# WeMosMid400Sensor.net
KiCad netlist of a schematic drawn in EAGLE
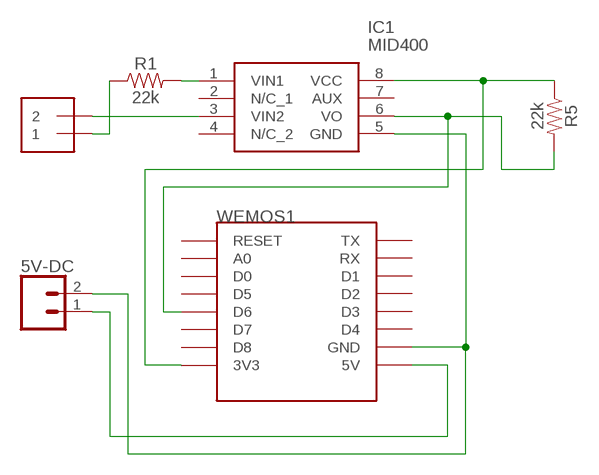
[diagram p0: schematic, sheet 1]

(export (version "E")
  (design (tool "Eeschema 10.0.6"))
  (components
    (comp (ref "5V-DC")
      (value "CONN_02")
      (footprint "eagle-import:1X02")
      (libsource (lib "eagle-import") (part "CONN_02"))
    )
    (comp (ref "A/C")
      (value "1X2-3.5MM")
      (footprint "eagle-import:1X2-3.5MM")
      (libsource (lib "eagle-import") (part "1X2-3.5MM"))
    )
    (comp (ref "IC1")
      (value "MID400")
      (footprint "eagle-import:DIP762W56P254L966H508Q8N")
      (fields (field (name "RS_PART_NUMBER") "7613962P"))
      (libsource (lib "eagle-import") (part "MID400"))
    )
    (comp (ref "R1")
      (value "22k")
      (footprint "eagle-import:AXIAL-0.3")
      (libsource (lib "eagle-import") (part "15KOHM-HORIZ-1/4W-5%"))
    )
    (comp (ref "R5")
      (value "22k")
      (footprint "eagle-import:AXIAL-0.3")
      (libsource (lib "eagle-import") (part "15KOHM-HORIZ-1/4W-5%"))
    )
    (comp (ref "WEMOS1")
      (value "WEMOS-D1-MINI")
      (footprint "eagle-import:WEMOS-D1-MINI")
      (libsource (lib "eagle-import") (part "WEMOS-D1-MINI"))
    )
  )
  (nets
    (net (code "1") (name "Net-(5V-DC-Pad1)") (class "Default")
      (node (ref "5V-DC") (pin "1") (pinfunction "1_1") (pintype "passive"))
      (node (ref "WEMOS1") (pin "5V") (pinfunction "5V_5V") (pintype "bidirectional"))
    )
    (net (code "2") (name "Net-(IC1-GND)") (class "Default")
      (node (ref "5V-DC") (pin "2") (pinfunction "2_2") (pintype "passive"))
      (node (ref "IC1") (pin "5") (pinfunction "GND_5") (pintype "bidirectional"))
      (node (ref "WEMOS1") (pin "GND") (pinfunction "GND_GND") (pintype "bidirectional"))
    )
    (net (code "3") (name "Net-(IC1-VCC)") (class "Default")
      (node (ref "IC1") (pin "8") (pinfunction "VCC_8") (pintype "bidirectional"))
      (node (ref "R5") (pin "P$1") (pinfunction "1_P$1") (pintype "passive"))
      (node (ref "WEMOS1") (pin "3V3") (pinfunction "3V3_3V3") (pintype "bidirectional"))
    )
    (net (code "4") (name "Net-(IC1-VIN1)") (class "Default")
      (node (ref "IC1") (pin "1") (pinfunction "VIN1_1") (pintype "bidirectional"))
      (node (ref "R1") (pin "P$2") (pinfunction "2_P$2") (pintype "passive"))
    )
    (net (code "5") (name "Net-(IC1-VIN2)") (class "Default")
      (node (ref "A/C") (pin "2") (pinfunction "2_2") (pintype "passive"))
      (node (ref "IC1") (pin "3") (pinfunction "VIN2_3") (pintype "bidirectional"))
    )
    (net (code "6") (name "Net-(IC1-VO)") (class "Default")
      (node (ref "IC1") (pin "6") (pinfunction "VO_6") (pintype "bidirectional"))
      (node (ref "R5") (pin "P$2") (pinfunction "2_P$2") (pintype "passive"))
      (node (ref "WEMOS1") (pin "D6") (pinfunction "D6_D6") (pintype "bidirectional"))
    )
    (net (code "7") (name "Net-(R1-1)") (class "Default")
      (node (ref "A/C") (pin "1") (pinfunction "1_1") (pintype "passive"))
      (node (ref "R1") (pin "P$1") (pinfunction "1_P$1") (pintype "passive"))
    )
    (net (code "8") (name "unconnected-(IC1-AUX-Pad7)") (class "Default")
      (node (ref "IC1") (pin "7") (pinfunction "AUX_7") (pintype "bidirectional"))
    )
    (net (code "9") (name "unconnected-(IC1-N{slash}C_1-Pad2)") (class "Default")
      (node (ref "IC1") (pin "2") (pinfunction "N/C_1_2") (pintype "bidirectional"))
    )
    (net (code "10") (name "unconnected-(IC1-N{slash}C_2-Pad4)") (class "Default")
      (node (ref "IC1") (pin "4") (pinfunction "N/C_2_4") (pintype "bidirectional"))
    )
    (net (code "11") (name "unconnected-(WEMOS1-PadA0)") (class "Default")
      (node (ref "WEMOS1") (pin "A0") (pinfunction "A0_A0") (pintype "bidirectional"))
    )
    (net (code "12") (name "unconnected-(WEMOS1-PadD0)") (class "Default")
      (node (ref "WEMOS1") (pin "D0") (pinfunction "D0_D0") (pintype "bidirectional"))
    )
    (net (code "13") (name "unconnected-(WEMOS1-PadD1)") (class "Default")
      (node (ref "WEMOS1") (pin "D1") (pinfunction "D1_D1") (pintype "bidirectional"))
    )
    (net (code "14") (name "unconnected-(WEMOS1-PadD2)") (class "Default")
      (node (ref "WEMOS1") (pin "D2") (pinfunction "D2_D2") (pintype "bidirectional"))
    )
    (net (code "15") (name "unconnected-(WEMOS1-PadD3)") (class "Default")
      (node (ref "WEMOS1") (pin "D3") (pinfunction "D3_D3") (pintype "bidirectional"))
    )
    (net (code "16") (name "unconnected-(WEMOS1-PadD4)") (class "Default")
      (node (ref "WEMOS1") (pin "D4") (pinfunction "D4_D4") (pintype "bidirectional"))
    )
    (net (code "17") (name "unconnected-(WEMOS1-PadD5)") (class "Default")
      (node (ref "WEMOS1") (pin "D5") (pinfunction "D5_D5") (pintype "bidirectional"))
    )
    (net (code "18") (name "unconnected-(WEMOS1-PadD7)") (class "Default")
      (node (ref "WEMOS1") (pin "D7") (pinfunction "D7_D7") (pintype "bidirectional"))
    )
    (net (code "19") (name "unconnected-(WEMOS1-PadD8)") (class "Default")
      (node (ref "WEMOS1") (pin "D8") (pinfunction "D8_D8") (pintype "bidirectional"))
    )
    (net (code "20") (name "unconnected-(WEMOS1-PadRESET)") (class "Default")
      (node (ref "WEMOS1") (pin "RESET") (pinfunction "RESET_RESET") (pintype "bidirectional"))
    )
    (net (code "21") (name "unconnected-(WEMOS1-PadRX)") (class "Default")
      (node (ref "WEMOS1") (pin "RX") (pinfunction "RX_RX") (pintype "bidirectional"))
    )
    (net (code "22") (name "unconnected-(WEMOS1-PadTX)") (class "Default")
      (node (ref "WEMOS1") (pin "TX") (pinfunction "TX_TX") (pintype "bidirectional"))
    )
  )
)
